# TLSR8258_Module.net
KiCad netlist of a schematic drawn in Altium Designer
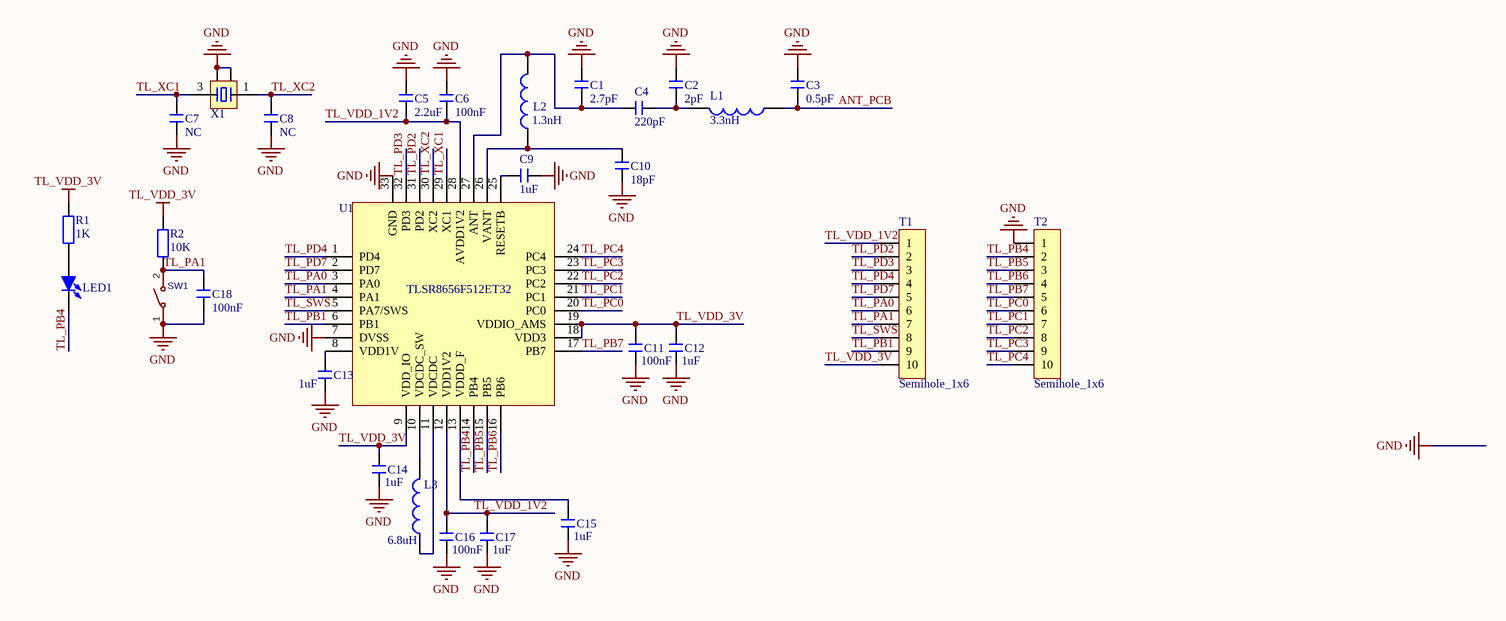
[diagram p0: TLSR8258_Module.SchDoc]

(export (version "E")
  (design (tool "Eeschema 10.0.6"))
  (components
    (comp (ref "C1")
      (value "2.7pF")
      (footprint "C 0402_L")
      (description "贴片电容")
      (libsource (lib "Lx_Whole_Lock") (part "C"))
    )
    (comp (ref "C2")
      (value "2pF")
      (footprint "C 0402_L")
      (description "贴片电容")
      (libsource (lib "Lx_Whole_Lock") (part "C"))
    )
    (comp (ref "C3")
      (value "0.5pF")
      (footprint "C 0402_L")
      (description "贴片电容")
      (libsource (lib "Lx_Whole_Lock") (part "C"))
    )
    (comp (ref "C4")
      (value "220pF")
      (footprint "C 0402_L")
      (description "贴片电容")
      (libsource (lib "Lx_Whole_Lock") (part "C"))
    )
    (comp (ref "C5")
      (value "2.2uF")
      (footprint "C 0402_L")
      (description "贴片电容")
      (libsource (lib "Lx_Whole_Lock") (part "C"))
    )
    (comp (ref "C6")
      (value "100nF")
      (footprint "C 0402_L")
      (description "贴片电容")
      (libsource (lib "Lx_Whole_Lock") (part "C"))
    )
    (comp (ref "C7")
      (value "NC")
      (footprint "C 0402_L")
      (description "贴片电容")
      (libsource (lib "Lx_Whole_Lock") (part "C"))
    )
    (comp (ref "C8")
      (value "NC")
      (footprint "C 0402_L")
      (description "贴片电容")
      (libsource (lib "Lx_Whole_Lock") (part "C"))
    )
    (comp (ref "C9")
      (value "1uF")
      (footprint "C 0402_L")
      (description "贴片电容")
      (libsource (lib "Lx_Whole_Lock") (part "C"))
    )
    (comp (ref "C10")
      (value "18pF")
      (footprint "C 0402_L")
      (description "贴片电容")
      (libsource (lib "Lx_Whole_Lock") (part "C"))
    )
    (comp (ref "C11")
      (value "100nF")
      (footprint "C 0402_L")
      (description "贴片电容")
      (libsource (lib "Lx_Whole_Lock") (part "C"))
    )
    (comp (ref "C12")
      (value "1uF")
      (footprint "C 0402_L")
      (description "贴片电容")
      (libsource (lib "Lx_Whole_Lock") (part "C"))
    )
    (comp (ref "C13")
      (value "1uF")
      (footprint "C 0402_L")
      (description "贴片电容")
      (libsource (lib "Lx_Whole_Lock") (part "C"))
    )
    (comp (ref "C14")
      (value "1uF")
      (footprint "C 0402_L")
      (description "贴片电容")
      (libsource (lib "Lx_Whole_Lock") (part "C"))
    )
    (comp (ref "C15")
      (value "1uF")
      (footprint "C 0402_L")
      (description "贴片电容")
      (libsource (lib "Lx_Whole_Lock") (part "C"))
    )
    (comp (ref "C16")
      (value "100nF")
      (footprint "C 0402_L")
      (description "贴片电容")
      (libsource (lib "Lx_Whole_Lock") (part "C"))
    )
    (comp (ref "C17")
      (value "1uF")
      (footprint "C 0402_L")
      (description "贴片电容")
      (libsource (lib "Lx_Whole_Lock") (part "C"))
    )
    (comp (ref "C18")
      (value "100nF")
      (footprint "C 0402_L")
      (description "贴片电容")
      (libsource (lib "Lx_Whole_Lock") (part "C"))
    )
    (comp (ref "L1")
      (value "3.3nH")
      (footprint "L 0402")
      (description "小功率贴片电感")
      (libsource (lib "TLSR8258_Module") (part "L"))
    )
    (comp (ref "L2")
      (value "1.3nH")
      (footprint "L 0402")
      (description "小功率贴片电感")
      (libsource (lib "TLSR8258_Module") (part "L"))
    )
    (comp (ref "L3")
      (value "6.8uH")
      (footprint "L 0603")
      (description "小功率贴片电感")
      (libsource (lib "TLSR8258_Module") (part "L"))
    )
    (comp (ref "LED1")
      (value "LED")
      (footprint "LED0402-RD")
      (libsource (lib "TLSR8258_Module") (part "LED"))
    )
    (comp (ref "R1")
      (value "1K")
      (footprint "R 0402_L")
      (description "贴片电阻")
      (libsource (lib "Lx_Whole_Lock") (part "R"))
    )
    (comp (ref "R2")
      (value "10K")
      (footprint "R 0402_L")
      (description "贴片电阻")
      (libsource (lib "Lx_Whole_Lock") (part "R"))
    )
    (comp (ref "SW1")
      (value "TS-1088R-02026")
      (footprint "SW-SMD_L3.9-W3.0-P4.45")
      (fields (field (name "MANUFACTURER") "XUNPU(讯普)"))
      (libsource (lib "TLSR8258_Module") (part "TS-1088R-02026"))
    )
    (comp (ref "T1")
      (value "Semihole_1x6")
      (footprint "SEMIHOLE_1x10")
      (libsource (lib "TLSR8258_Module") (part "Semihole_1x10"))
    )
    (comp (ref "T2")
      (value "Semihole_1x6")
      (footprint "SEMIHOLE_1x10")
      (libsource (lib "TLSR8258_Module") (part "Semihole_1x10"))
    )
    (comp (ref "U1")
      (value "TLSR8656F512ET32")
      (footprint "QFN32 5x5_L")
      (libsource (lib "TLSR8258_Module") (part "TLSR8656F512ET32"))
    )
    (comp (ref "X1")
      (value "TAXM24M4ZFBCCT2T")
      (footprint "OSC 3225-4P")
      (description "4脚无源晶振(24M)")
      (libsource (lib "TLSR8258_Module") (part "XTAL-4P"))
    )
  )
  (nets
    (net (code "1") (name "/ANT_PCB") (class "Default")
      (node (ref "C3") (pin "2") (pinfunction "2_2") (pintype "passive"))
      (node (ref "L1") (pin "1") (pinfunction "1_1") (pintype "passive"))
    )
    (net (code "2") (name "/TL_PA0") (class "Default")
      (node (ref "T1") (pin "6") (pinfunction "6_6") (pintype "passive"))
      (node (ref "U1") (pin "3") (pinfunction "PA0_3") (pintype "passive"))
    )
    (net (code "3") (name "/TL_PA1") (class "Default")
      (node (ref "C18") (pin "2") (pinfunction "2_2") (pintype "passive"))
      (node (ref "R2") (pin "1") (pinfunction "1_1") (pintype "passive"))
      (node (ref "SW1") (pin "2") (pinfunction "2_2") (pintype "passive"))
      (node (ref "T1") (pin "7") (pinfunction "7_7") (pintype "passive"))
      (node (ref "U1") (pin "4") (pinfunction "PA1_4") (pintype "passive"))
    )
    (net (code "4") (name "/TL_PB1") (class "Default")
      (node (ref "T1") (pin "9") (pinfunction "9_9") (pintype "passive"))
      (node (ref "U1") (pin "6") (pinfunction "PB1_6") (pintype "passive"))
    )
    (net (code "5") (name "/TL_PB4") (class "Default")
      (node (ref "LED1") (pin "1") (pinfunction "K_1") (pintype "passive"))
      (node (ref "T2") (pin "2") (pinfunction "2_2") (pintype "passive"))
      (node (ref "U1") (pin "14") (pinfunction "PB4_14") (pintype "passive"))
    )
    (net (code "6") (name "/TL_PB5") (class "Default")
      (node (ref "T2") (pin "3") (pinfunction "3_3") (pintype "passive"))
      (node (ref "U1") (pin "15") (pinfunction "PB5_15") (pintype "passive"))
    )
    (net (code "7") (name "/TL_PB6") (class "Default")
      (node (ref "T2") (pin "4") (pinfunction "4_4") (pintype "passive"))
      (node (ref "U1") (pin "16") (pinfunction "PB6_16") (pintype "passive"))
    )
    (net (code "8") (name "/TL_PB7") (class "Default")
      (node (ref "T2") (pin "5") (pinfunction "5_5") (pintype "passive"))
      (node (ref "U1") (pin "17") (pinfunction "PB7_17") (pintype "passive"))
    )
    (net (code "9") (name "/TL_PC0") (class "Default")
      (node (ref "T2") (pin "6") (pinfunction "6_6") (pintype "passive"))
      (node (ref "U1") (pin "20") (pinfunction "PC0_20") (pintype "passive"))
    )
    (net (code "10") (name "/TL_PC1") (class "Default")
      (node (ref "T2") (pin "7") (pinfunction "7_7") (pintype "passive"))
      (node (ref "U1") (pin "21") (pinfunction "PC1_21") (pintype "passive"))
    )
    (net (code "11") (name "/TL_PC2") (class "Default")
      (node (ref "T2") (pin "8") (pinfunction "8_8") (pintype "passive"))
      (node (ref "U1") (pin "22") (pinfunction "PC2_22") (pintype "passive"))
    )
    (net (code "12") (name "/TL_PC3") (class "Default")
      (node (ref "T2") (pin "9") (pinfunction "9_9") (pintype "passive"))
      (node (ref "U1") (pin "23") (pinfunction "PC3_23") (pintype "passive"))
    )
    (net (code "13") (name "/TL_PC4") (class "Default")
      (node (ref "T2") (pin "10") (pinfunction "10_10") (pintype "passive"))
      (node (ref "U1") (pin "24") (pinfunction "PC4_24") (pintype "passive"))
    )
    (net (code "14") (name "/TL_PD2") (class "Default")
      (node (ref "T1") (pin "2") (pinfunction "2_2") (pintype "passive"))
      (node (ref "U1") (pin "31") (pinfunction "PD2_31") (pintype "passive"))
    )
    (net (code "15") (name "/TL_PD3") (class "Default")
      (node (ref "T1") (pin "3") (pinfunction "3_3") (pintype "passive"))
      (node (ref "U1") (pin "32") (pinfunction "PD3_32") (pintype "passive"))
    )
    (net (code "16") (name "/TL_PD4") (class "Default")
      (node (ref "T1") (pin "4") (pinfunction "4_4") (pintype "passive"))
      (node (ref "U1") (pin "1") (pinfunction "PD4_1") (pintype "passive"))
    )
    (net (code "17") (name "/TL_PD7") (class "Default")
      (node (ref "T1") (pin "5") (pinfunction "5_5") (pintype "passive"))
      (node (ref "U1") (pin "2") (pinfunction "PD7_2") (pintype "passive"))
    )
    (net (code "18") (name "/TL_SWS") (class "Default")
      (node (ref "T1") (pin "8") (pinfunction "8_8") (pintype "passive"))
      (node (ref "U1") (pin "5") (pinfunction "PA7/SWS_5") (pintype "passive"))
    )
    (net (code "19") (name "/TL_VDD_1V2") (class "Default")
      (node (ref "C16") (pin "2") (pinfunction "2_2") (pintype "passive"))
      (node (ref "C17") (pin "2") (pinfunction "2_2") (pintype "passive"))
      (node (ref "C5") (pin "2") (pinfunction "2_2") (pintype "passive"))
      (node (ref "C6") (pin "2") (pinfunction "2_2") (pintype "passive"))
      (node (ref "T1") (pin "1") (pinfunction "1_1") (pintype "passive"))
      (node (ref "U1") (pin "12") (pinfunction "VDD1V2_12") (pintype "passive"))
      (node (ref "U1") (pin "28") (pinfunction "AVDD1V2_28") (pintype "passive"))
    )
    (net (code "20") (name "/TL_XC1") (class "Default")
      (node (ref "C7") (pin "2") (pinfunction "2_2") (pintype "passive"))
      (node (ref "U1") (pin "29") (pinfunction "XC1_29") (pintype "passive"))
      (node (ref "X1") (pin "3") (pinfunction "3_3") (pintype "passive"))
    )
    (net (code "21") (name "/TL_XC2") (class "Default")
      (node (ref "C8") (pin "2") (pinfunction "2_2") (pintype "passive"))
      (node (ref "U1") (pin "30") (pinfunction "XC2_30") (pintype "passive"))
      (node (ref "X1") (pin "1") (pinfunction "1_1") (pintype "passive"))
    )
    (net (code "22") (name "GND") (class "Default")
      (node (ref "C1") (pin "1") (pinfunction "1_1") (pintype "passive"))
      (node (ref "C10") (pin "2") (pinfunction "2_2") (pintype "passive"))
      (node (ref "C11") (pin "1") (pinfunction "1_1") (pintype "passive"))
      (node (ref "C12") (pin "1") (pinfunction "1_1") (pintype "passive"))
      (node (ref "C13") (pin "1") (pinfunction "1_1") (pintype "passive"))
      (node (ref "C14") (pin "1") (pinfunction "1_1") (pintype "passive"))
      (node (ref "C15") (pin "1") (pinfunction "1_1") (pintype "passive"))
      (node (ref "C16") (pin "1") (pinfunction "1_1") (pintype "passive"))
      (node (ref "C17") (pin "1") (pinfunction "1_1") (pintype "passive"))
      (node (ref "C18") (pin "1") (pinfunction "1_1") (pintype "passive"))
      (node (ref "C2") (pin "1") (pinfunction "1_1") (pintype "passive"))
      (node (ref "C3") (pin "1") (pinfunction "1_1") (pintype "passive"))
      (node (ref "C5") (pin "1") (pinfunction "1_1") (pintype "passive"))
      (node (ref "C6") (pin "1") (pinfunction "1_1") (pintype "passive"))
      (node (ref "C7") (pin "1") (pinfunction "1_1") (pintype "passive"))
      (node (ref "C8") (pin "1") (pinfunction "1_1") (pintype "passive"))
      (node (ref "C9") (pin "1") (pinfunction "1_1") (pintype "passive"))
      (node (ref "SW1") (pin "1") (pinfunction "1_1") (pintype "passive"))
      (node (ref "T2") (pin "1") (pinfunction "1_1") (pintype "passive"))
      (node (ref "U1") (pin "33") (pinfunction "GND_33") (pintype "passive"))
      (node (ref "U1") (pin "7") (pinfunction "DVSS_7") (pintype "passive"))
      (node (ref "X1") (pin "2") (pinfunction "2_2") (pintype "passive"))
      (node (ref "X1") (pin "4") (pinfunction "4_4") (pintype "passive"))
    )
    (net (code "23") (name "Net-(C2-Pad2)") (class "Default")
      (node (ref "C2") (pin "2") (pinfunction "2_2") (pintype "passive"))
      (node (ref "C4") (pin "2") (pinfunction "2_2") (pintype "passive"))
      (node (ref "L1") (pin "2") (pinfunction "2_2") (pintype "passive"))
    )
    (net (code "24") (name "Net-(LED1-A)") (class "Default")
      (node (ref "LED1") (pin "2") (pinfunction "A_2") (pintype "passive"))
      (node (ref "R1") (pin "1") (pinfunction "1_1") (pintype "passive"))
    )
    (net (code "25") (name "Net-(U1-ANT)") (class "Default")
      (node (ref "C1") (pin "2") (pinfunction "2_2") (pintype "passive"))
      (node (ref "C4") (pin "1") (pinfunction "1_1") (pintype "passive"))
      (node (ref "L2") (pin "2") (pinfunction "2_2") (pintype "passive"))
      (node (ref "U1") (pin "27") (pinfunction "ANT_27") (pintype "passive"))
    )
    (net (code "26") (name "Net-(U1-RESETB)") (class "Default")
      (node (ref "C9") (pin "2") (pinfunction "2_2") (pintype "passive"))
      (node (ref "U1") (pin "25") (pinfunction "RESETB_25") (pintype "passive"))
    )
    (net (code "27") (name "Net-(U1-VANT)") (class "Default")
      (node (ref "C10") (pin "1") (pinfunction "1_1") (pintype "passive"))
      (node (ref "L2") (pin "1") (pinfunction "1_1") (pintype "passive"))
      (node (ref "U1") (pin "26") (pinfunction "VANT_26") (pintype "passive"))
    )
    (net (code "28") (name "Net-(U1-VDCDC)") (class "Default")
      (node (ref "L3") (pin "1") (pinfunction "1_1") (pintype "passive"))
      (node (ref "U1") (pin "11") (pinfunction "VDCDC_11") (pintype "passive"))
    )
    (net (code "29") (name "Net-(U1-VDCDC_SW)") (class "Default")
      (node (ref "L3") (pin "2") (pinfunction "2_2") (pintype "passive"))
      (node (ref "U1") (pin "10") (pinfunction "VDCDC_SW_10") (pintype "passive"))
    )
    (net (code "30") (name "Net-(U1-VDD1V)") (class "Default")
      (node (ref "C13") (pin "2") (pinfunction "2_2") (pintype "passive"))
      (node (ref "U1") (pin "8") (pinfunction "VDD1V_8") (pintype "passive"))
    )
    (net (code "31") (name "Net-(U1-VDDD_F)") (class "Default")
      (node (ref "C15") (pin "2") (pinfunction "2_2") (pintype "passive"))
      (node (ref "U1") (pin "13") (pinfunction "VDDD_F_13") (pintype "passive"))
    )
    (net (code "32") (name "TL_VDD_3V") (class "Default")
      (node (ref "C11") (pin "2") (pinfunction "2_2") (pintype "passive"))
      (node (ref "C12") (pin "2") (pinfunction "2_2") (pintype "passive"))
      (node (ref "C14") (pin "2") (pinfunction "2_2") (pintype "passive"))
      (node (ref "R1") (pin "2") (pinfunction "2_2") (pintype "passive"))
      (node (ref "R2") (pin "2") (pinfunction "2_2") (pintype "passive"))
      (node (ref "T1") (pin "10") (pinfunction "10_10") (pintype "passive"))
      (node (ref "U1") (pin "18") (pinfunction "VDD3_18") (pintype "passive"))
      (node (ref "U1") (pin "19") (pinfunction "VDDIO_AMS_19") (pintype "passive"))
      (node (ref "U1") (pin "9") (pinfunction "VDD_IO_9") (pintype "passive"))
    )
  )
)
